# PokeDuino.net
KiCad netlist of a schematic drawn in EAGLE
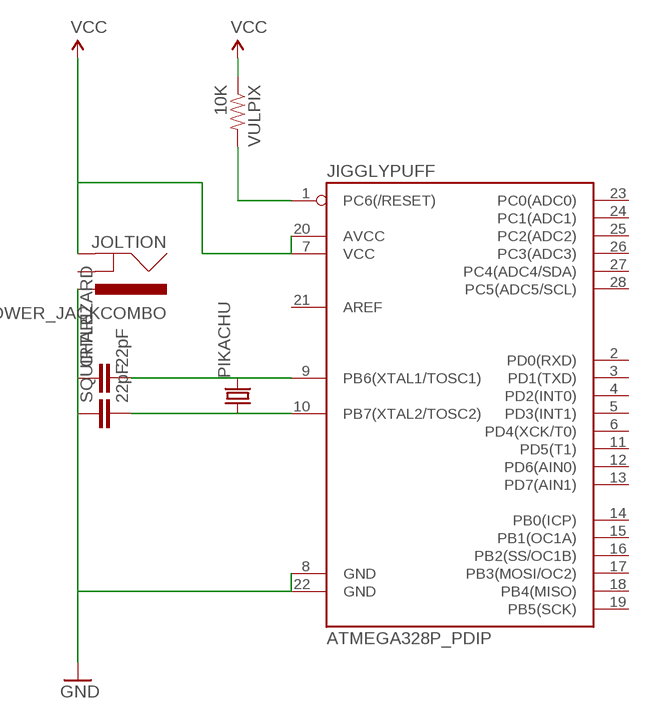
[diagram p0: schematic, sheet 1]

(export (version "E")
  (design (tool "Eeschema 10.0.6"))
  (components
    (comp (ref "CHARIZARD")
      (value "22pF")
      (footprint "eagle-import:CAP-PTH-5MM")
      (libsource (lib "eagle-import") (part "CAPPTH1"))
    )
    (comp (ref "JIGGLYPUFF")
      (value "ATMEGA328P_PDIP")
      (footprint "eagle-import:DIL28-3")
      (libsource (lib "eagle-import") (part "ATMEGA328P_PDIP"))
    )
    (comp (ref "JOLTION")
      (value "POWER_JACKCOMBO")
      (footprint "eagle-import:POWER_JACK_COMBO")
      (libsource (lib "eagle-import") (part "POWER_JACKCOMBO"))
    )
    (comp (ref "PIKACHU")
      (value "CRYSTALHC49UV")
      (footprint "eagle-import:HC49U-V")
      (libsource (lib "eagle-import") (part "CRYSTALHC49UV"))
    )
    (comp (ref "SQUIRTLE")
      (value "22pF")
      (footprint "eagle-import:CAP-PTH-5MM")
      (libsource (lib "eagle-import") (part "CAPPTH1"))
    )
    (comp (ref "VULPIX")
      (value "10K")
      (footprint "eagle-import:AXIAL-0.4")
      (libsource (lib "eagle-import") (part "RESISTORPTH-1/4W"))
    )
  )
  (nets
    (net (code "1") (name "GND") (class "Default")
      (node (ref "CHARIZARD") (pin "1") (pinfunction "1_1") (pintype "passive"))
      (node (ref "JIGGLYPUFF") (pin "22") (pinfunction "GND_22") (pintype "bidirectional"))
      (node (ref "JIGGLYPUFF") (pin "8") (pinfunction "GND_8") (pintype "bidirectional"))
      (node (ref "JOLTION") (pin "POWER") (pinfunction "PWR_POWER") (pintype "bidirectional"))
      (node (ref "SQUIRTLE") (pin "1") (pinfunction "1_1") (pintype "passive"))
    )
    (net (code "2") (name "Net-(JIGGLYPUFF-PB6(XTAL1{slash}TOSC1))") (class "Default")
      (node (ref "CHARIZARD") (pin "2") (pinfunction "2_2") (pintype "passive"))
      (node (ref "JIGGLYPUFF") (pin "9") (pinfunction "PB6(XTAL1/TOSC1)_9") (pintype "bidirectional"))
      (node (ref "PIKACHU") (pin "2") (pinfunction "2_2") (pintype "passive"))
    )
    (net (code "3") (name "Net-(JIGGLYPUFF-PB7(XTAL2{slash}TOSC2))") (class "Default")
      (node (ref "JIGGLYPUFF") (pin "10") (pinfunction "PB7(XTAL2/TOSC2)_10") (pintype "bidirectional"))
      (node (ref "PIKACHU") (pin "1") (pinfunction "1_1") (pintype "passive"))
      (node (ref "SQUIRTLE") (pin "2") (pinfunction "2_2") (pintype "passive"))
    )
    (net (code "4") (name "Net-(JIGGLYPUFF-PC6({slash}RESET))") (class "Default")
      (node (ref "JIGGLYPUFF") (pin "1") (pinfunction "PC6(/RESET)_1") (pintype "bidirectional"))
      (node (ref "VULPIX") (pin "P$2") (pinfunction "2_P$2") (pintype "passive"))
    )
    (net (code "5") (name "VCC") (class "Default")
      (node (ref "JIGGLYPUFF") (pin "20") (pinfunction "AVCC_20") (pintype "bidirectional"))
      (node (ref "JIGGLYPUFF") (pin "7") (pinfunction "VCC_7") (pintype "bidirectional"))
      (node (ref "JOLTION") (pin "GND@1") (pinfunction "GND_GND@1") (pintype "bidirectional"))
      (node (ref "VULPIX") (pin "P$1") (pinfunction "1_P$1") (pintype "passive"))
    )
    (net (code "6") (name "unconnected-(JIGGLYPUFF-AREF-Pad21)") (class "Default")
      (node (ref "JIGGLYPUFF") (pin "21") (pinfunction "AREF_21") (pintype "bidirectional"))
    )
    (net (code "7") (name "unconnected-(JIGGLYPUFF-PB0(ICP)-Pad14)") (class "Default")
      (node (ref "JIGGLYPUFF") (pin "14") (pinfunction "PB0(ICP)_14") (pintype "bidirectional"))
    )
    (net (code "8") (name "unconnected-(JIGGLYPUFF-PB1(OC1A)-Pad15)") (class "Default")
      (node (ref "JIGGLYPUFF") (pin "15") (pinfunction "PB1(OC1A)_15") (pintype "bidirectional"))
    )
    (net (code "9") (name "unconnected-(JIGGLYPUFF-PB2(SS{slash}OC1B)-Pad16)") (class "Default")
      (node (ref "JIGGLYPUFF") (pin "16") (pinfunction "PB2(SS/OC1B)_16") (pintype "bidirectional"))
    )
    (net (code "10") (name "unconnected-(JIGGLYPUFF-PB3(MOSI{slash}OC2)-Pad17)") (class "Default")
      (node (ref "JIGGLYPUFF") (pin "17") (pinfunction "PB3(MOSI/OC2)_17") (pintype "bidirectional"))
    )
    (net (code "11") (name "unconnected-(JIGGLYPUFF-PB4(MISO)-Pad18)") (class "Default")
      (node (ref "JIGGLYPUFF") (pin "18") (pinfunction "PB4(MISO)_18") (pintype "bidirectional"))
    )
    (net (code "12") (name "unconnected-(JIGGLYPUFF-PB5(SCK)-Pad19)") (class "Default")
      (node (ref "JIGGLYPUFF") (pin "19") (pinfunction "PB5(SCK)_19") (pintype "bidirectional"))
    )
    (net (code "13") (name "unconnected-(JIGGLYPUFF-PC0(ADC0)-Pad23)") (class "Default")
      (node (ref "JIGGLYPUFF") (pin "23") (pinfunction "PC0(ADC0)_23") (pintype "bidirectional"))
    )
    (net (code "14") (name "unconnected-(JIGGLYPUFF-PC1(ADC1)-Pad24)") (class "Default")
      (node (ref "JIGGLYPUFF") (pin "24") (pinfunction "PC1(ADC1)_24") (pintype "bidirectional"))
    )
    (net (code "15") (name "unconnected-(JIGGLYPUFF-PC2(ADC2)-Pad25)") (class "Default")
      (node (ref "JIGGLYPUFF") (pin "25") (pinfunction "PC2(ADC2)_25") (pintype "bidirectional"))
    )
    (net (code "16") (name "unconnected-(JIGGLYPUFF-PC3(ADC3)-Pad26)") (class "Default")
      (node (ref "JIGGLYPUFF") (pin "26") (pinfunction "PC3(ADC3)_26") (pintype "bidirectional"))
    )
    (net (code "17") (name "unconnected-(JIGGLYPUFF-PC4(ADC4{slash}SDA)-Pad27)") (class "Default")
      (node (ref "JIGGLYPUFF") (pin "27") (pinfunction "PC4(ADC4/SDA)_27") (pintype "bidirectional"))
    )
    (net (code "18") (name "unconnected-(JIGGLYPUFF-PC5(ADC5{slash}SCL)-Pad28)") (class "Default")
      (node (ref "JIGGLYPUFF") (pin "28") (pinfunction "PC5(ADC5/SCL)_28") (pintype "bidirectional"))
    )
    (net (code "19") (name "unconnected-(JIGGLYPUFF-PD0(RXD)-Pad2)") (class "Default")
      (node (ref "JIGGLYPUFF") (pin "2") (pinfunction "PD0(RXD)_2") (pintype "bidirectional"))
    )
    (net (code "20") (name "unconnected-(JIGGLYPUFF-PD1(TXD)-Pad3)") (class "Default")
      (node (ref "JIGGLYPUFF") (pin "3") (pinfunction "PD1(TXD)_3") (pintype "bidirectional"))
    )
    (net (code "21") (name "unconnected-(JIGGLYPUFF-PD2(INT0)-Pad4)") (class "Default")
      (node (ref "JIGGLYPUFF") (pin "4") (pinfunction "PD2(INT0)_4") (pintype "bidirectional"))
    )
    (net (code "22") (name "unconnected-(JIGGLYPUFF-PD3(INT1)-Pad5)") (class "Default")
      (node (ref "JIGGLYPUFF") (pin "5") (pinfunction "PD3(INT1)_5") (pintype "bidirectional"))
    )
    (net (code "23") (name "unconnected-(JIGGLYPUFF-PD4(XCK{slash}T0)-Pad6)") (class "Default")
      (node (ref "JIGGLYPUFF") (pin "6") (pinfunction "PD4(XCK/T0)_6") (pintype "bidirectional"))
    )
    (net (code "24") (name "unconnected-(JIGGLYPUFF-PD5(T1)-Pad11)") (class "Default")
      (node (ref "JIGGLYPUFF") (pin "11") (pinfunction "PD5(T1)_11") (pintype "bidirectional"))
    )
    (net (code "25") (name "unconnected-(JIGGLYPUFF-PD6(AIN0)-Pad12)") (class "Default")
      (node (ref "JIGGLYPUFF") (pin "12") (pinfunction "PD6(AIN0)_12") (pintype "bidirectional"))
    )
    (net (code "26") (name "unconnected-(JIGGLYPUFF-PD7(AIN1)-Pad13)") (class "Default")
      (node (ref "JIGGLYPUFF") (pin "13") (pinfunction "PD7(AIN1)_13") (pintype "bidirectional"))
    )
    (net (code "27") (name "unconnected-(JOLTION-GNDBREAK-PadGND)") (class "Default")
      (node (ref "JOLTION") (pin "GND") (pinfunction "GNDBREAK_GND") (pintype "bidirectional"))
    )
  )
)
